# power_scm.net
KiCad netlist of a schematic drawn in Altium Designer
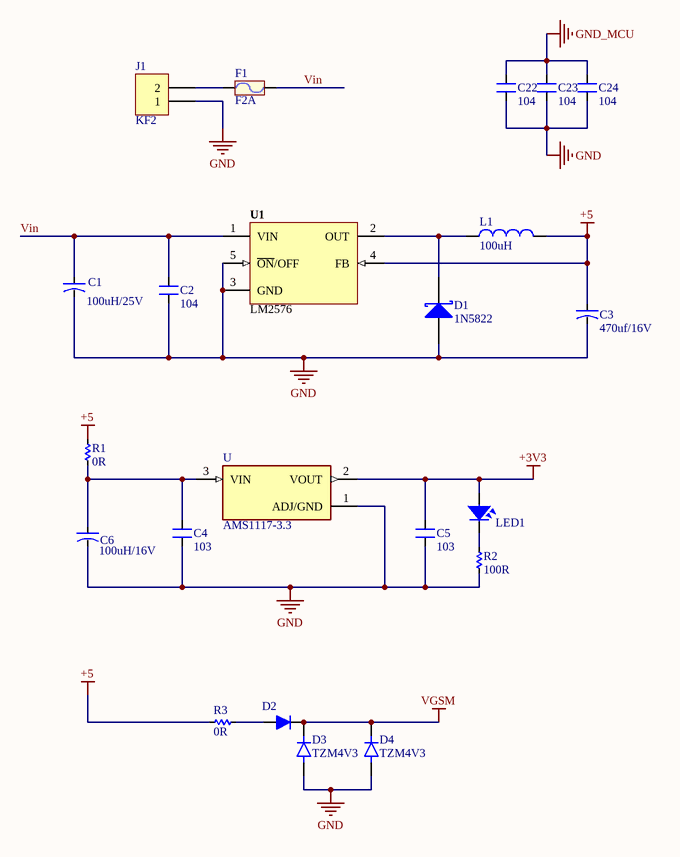
[diagram p0: power_scm.SchDoc]

(export (version "E")
  (design (tool "Eeschema 10.0.6"))
  (components
    (comp (ref "C1")
      (value "100uH/25V")
      (footprint "CAP-ALU-SMD-6.3x7.7x2.2")
      (description "Polarized Capacitor (Axial)")
      (fields (field (name "PUBLISHER") "Altium Limited"))
      (libsource (lib "TechMT.VN_Lib_Project v2") (part "CN-ALU-SMD"))
    )
    (comp (ref "C2")
      (value "104")
      (footprint "SM-0805")
      (description "Cap SMD")
      (libsource (lib "syhaunguyen") (part "CM"))
    )
    (comp (ref "C3")
      (value "470uf/16V")
      (footprint "CAP-ALU-SMD-6.3x7.7x2.2")
      (description "Polarized Capacitor (Axial)")
      (fields (field (name "PUBLISHER") "Altium Limited"))
      (libsource (lib "TechMT.VN_Lib_Project v2") (part "CN-ALU-SMD"))
    )
    (comp (ref "C4")
      (value "103")
      (footprint "SM-0805")
      (description "Cap SMD")
      (libsource (lib "syhaunguyen") (part "CM"))
    )
    (comp (ref "C5")
      (value "103")
      (footprint "SM-0805")
      (description "Cap SMD")
      (libsource (lib "syhaunguyen") (part "CM"))
    )
    (comp (ref "C6")
      (value "100uH/16V")
      (footprint "CAP-ALU-SMD-6.3x7.7x2.2")
      (description "Polarized Capacitor (Axial)")
      (fields (field (name "PUBLISHER") "Altium Limited"))
      (libsource (lib "TechMT.VN_Lib_Project v2") (part "CN-ALU-SMD"))
    )
    (comp (ref "C22")
      (value "104")
      (footprint "SM-0805")
      (description "Cap SMD")
      (libsource (lib "syhaunguyen") (part "CM"))
    )
    (comp (ref "C23")
      (value "104")
      (footprint "SM-0805")
      (description "Cap SMD")
      (libsource (lib "syhaunguyen") (part "CM"))
    )
    (comp (ref "C24")
      (value "104")
      (footprint "SM-0805")
      (description "Cap SMD")
      (libsource (lib "syhaunguyen") (part "CM"))
    )
    (comp (ref "D1")
      (value "1N5822")
      (footprint "Diode_SS34")
      (description "Schottky diode")
      (libsource (lib "AYRIC Library") (part "1N5819"))
    )
    (comp (ref "D2")
      (value "~")
      (footprint "1N4007_SMD")
      (description "diode")
      (libsource (lib "oggy") (part "diode"))
    )
    (comp (ref "D3")
      (value "TZM4V3")
      (footprint "DIO_LL4148")
      (description "Diode Standard 100V 200mA Surface Mount SOD-80")
      (fields (field (name "MP") "LL4148") (field (name "MF") "ON Semiconductor"))
      (libsource (lib "LL4148") (part "LL4148"))
    )
    (comp (ref "D4")
      (value "TZM4V3")
      (footprint "DIO_LL4148")
      (description "Diode Standard 100V 200mA Surface Mount SOD-80")
      (fields (field (name "MP") "LL4148") (field (name "MF") "ON Semiconductor"))
      (libsource (lib "LL4148") (part "LL4148"))
    )
    (comp (ref "F1")
      (value "F2A")
      (footprint "FUSE2")
      (description "Fuse")
      (fields (field (name "DESIGNED BY") "VanDungEvn"))
      (libsource (lib "TechMT.VN_Lib_Project v2") (part "Fuse"))
    )
    (comp (ref "J1")
      (value "KF2")
      (footprint "KF2-5.08")
      (fields
        (field (name "MANUFACTURER") "Würth Elektronik eiSos GmbH")
        (field (name "PARTNO") "691103110002")
        (field (name "CREATED BY") "Karrer Zheng")
      )
      (libsource (lib "TechMT.VN_Lib_Project v2") (part "KF2"))
    )
    (comp (ref "L1")
      (value "100uH")
      (footprint "inductor_smd")
      (fields (field (name "Comment") "Inductor") (field (name "PUBLISHER") "Altium Limited"))
      (libsource (lib "AYRIC Library") (part "Inductor"))
    )
    (comp (ref "LED1")
      (value "LED")
      (footprint "LED-0805-Green")
      (libsource (lib "TechMT.VN_Lib_Project v2") (part "LED SMD"))
    )
    (comp (ref "R1")
      (value "0R")
      (footprint "RES-SMD-0805")
      (description "Resistor")
      (fields
        (field (name "MANUFACTURER") "Generic Components")
        (field (name "PUBLISHER") "Altium Hobart Technology Centre")
      )
      (libsource (lib "TechMT.VN_Lib_Project v2") (part "Res-SMD"))
    )
    (comp (ref "R2")
      (value "100R")
      (footprint "RES-SMD-0805")
      (description "Resistor")
      (fields
        (field (name "MANUFACTURER") "Generic Components")
        (field (name "PUBLISHER") "Altium Hobart Technology Centre")
      )
      (libsource (lib "TechMT.VN_Lib_Project v2") (part "Res-SMD"))
    )
    (comp (ref "R3")
      (value "0R")
      (footprint "RES-SMD-0805")
      (description "Resistor")
      (fields
        (field (name "MANUFACTURER") "Generic Components")
        (field (name "PUBLISHER") "Altium Hobart Technology Centre")
      )
      (libsource (lib "TechMT.VN_Lib_Project v2") (part "Res-SMD"))
    )
    (comp (ref "U")
      (value "AMS1117-3.3")
      (footprint "SOT229P700X180-4N")
      (description "Sot223/Pkg 1-Amp 3.3-Volt Low Drop Out Voltage Regulatator")
      (fields (field (name "MF") "Advanced Monolithic Systems"))
      (libsource (lib "AMS1117-3.3") (part "AMS1117-3.3"))
    )
    (comp (ref "U1")
      (value "LM2576")
      (footprint "TO263")
      (libsource (lib "TechMT.VN_Lib_Project v2") (part "LM2576"))
    )
  )
  (nets
    (net (code "1") (name "+3V3") (class "Default")
      (node (ref "C5") (pin "1") (pinfunction "1_1") (pintype "passive"))
      (node (ref "LED1") (pin "1") (pinfunction "1_1") (pintype "passive"))
      (node (ref "U") (pin "2") (pinfunction "VOUT_2") (pintype "output"))
    )
    (net (code "2") (name "+5") (class "Default")
      (node (ref "C3") (pin "1") (pinfunction "1_1") (pintype "passive"))
      (node (ref "L1") (pin "2") (pinfunction "2_2") (pintype "passive"))
      (node (ref "R1") (pin "1") (pinfunction "1_1") (pintype "passive"))
      (node (ref "R3") (pin "1") (pinfunction "1_1") (pintype "passive"))
      (node (ref "U1") (pin "4") (pinfunction "FB_4") (pintype "input"))
    )
    (net (code "3") (name "/Vin") (class "Default")
      (node (ref "C1") (pin "1") (pinfunction "1_1") (pintype "passive"))
      (node (ref "C2") (pin "1") (pinfunction "1_1") (pintype "passive"))
      (node (ref "F1") (pin "2") (pinfunction "2_2") (pintype "passive"))
      (node (ref "U1") (pin "1") (pinfunction "VIN_1") (pintype "power_in"))
    )
    (net (code "4") (name "GND") (class "Default")
      (node (ref "C1") (pin "2") (pinfunction "2_2") (pintype "passive"))
      (node (ref "C2") (pin "2") (pinfunction "2_2") (pintype "passive"))
      (node (ref "C22") (pin "1") (pinfunction "1_1") (pintype "passive"))
      (node (ref "C23") (pin "1") (pinfunction "1_1") (pintype "passive"))
      (node (ref "C24") (pin "1") (pinfunction "1_1") (pintype "passive"))
      (node (ref "C3") (pin "2") (pinfunction "2_2") (pintype "passive"))
      (node (ref "C4") (pin "2") (pinfunction "2_2") (pintype "passive"))
      (node (ref "C5") (pin "2") (pinfunction "2_2") (pintype "passive"))
      (node (ref "C6") (pin "2") (pinfunction "2_2") (pintype "passive"))
      (node (ref "D1") (pin "1") (pinfunction "A_1") (pintype "passive"))
      (node (ref "D3") (pin "A") (pinfunction "A_A") (pintype "passive"))
      (node (ref "D4") (pin "A") (pinfunction "A_A") (pintype "passive"))
      (node (ref "J1") (pin "1") (pinfunction "1_1") (pintype "passive"))
      (node (ref "R2") (pin "2") (pinfunction "2_2") (pintype "passive"))
      (node (ref "U") (pin "1") (pinfunction "ADJ/GND_1") (pintype "power_in"))
      (node (ref "U1") (pin "3") (pinfunction "GND_3") (pintype "power_in"))
      (node (ref "U1") (pin "5") (pinfunction "~{ON}/OFF_5") (pintype "input"))
    )
    (net (code "5") (name "GND_MCU") (class "Default")
      (node (ref "C22") (pin "2") (pinfunction "2_2") (pintype "passive"))
      (node (ref "C23") (pin "2") (pinfunction "2_2") (pintype "passive"))
      (node (ref "C24") (pin "2") (pinfunction "2_2") (pintype "passive"))
    )
    (net (code "6") (name "Net-(D1-K)") (class "Default")
      (node (ref "D1") (pin "2") (pinfunction "K_2") (pintype "passive"))
      (node (ref "L1") (pin "1") (pinfunction "1_1") (pintype "passive"))
      (node (ref "U1") (pin "2") (pinfunction "OUT_2") (pintype "power_in"))
    )
    (net (code "7") (name "Net-(D2-Pad1)") (class "Default")
      (node (ref "D2") (pin "1") (pinfunction "1_1") (pintype "passive"))
      (node (ref "R3") (pin "2") (pinfunction "2_2") (pintype "passive"))
    )
    (net (code "8") (name "Net-(F1-Pad1)") (class "Default")
      (node (ref "F1") (pin "1") (pinfunction "1_1") (pintype "passive"))
      (node (ref "J1") (pin "2") (pinfunction "2_2") (pintype "passive"))
    )
    (net (code "9") (name "Net-(LED1-Pad2)") (class "Default")
      (node (ref "LED1") (pin "2") (pinfunction "2_2") (pintype "passive"))
      (node (ref "R2") (pin "1") (pinfunction "1_1") (pintype "passive"))
    )
    (net (code "10") (name "Net-(U-VIN)") (class "Default")
      (node (ref "C4") (pin "1") (pinfunction "1_1") (pintype "passive"))
      (node (ref "C6") (pin "1") (pinfunction "1_1") (pintype "passive"))
      (node (ref "R1") (pin "2") (pinfunction "2_2") (pintype "passive"))
      (node (ref "U") (pin "3") (pinfunction "VIN_3") (pintype "input"))
    )
    (net (code "11") (name "VGSM") (class "Default")
      (node (ref "D2") (pin "2") (pinfunction "2_2") (pintype "passive"))
      (node (ref "D3") (pin "C") (pinfunction "C_C") (pintype "passive"))
      (node (ref "D4") (pin "C") (pinfunction "C_C") (pintype "passive"))
    )
  )
)
